# RespirationSchematics.net
KiCad netlist of a schematic drawn in EAGLE
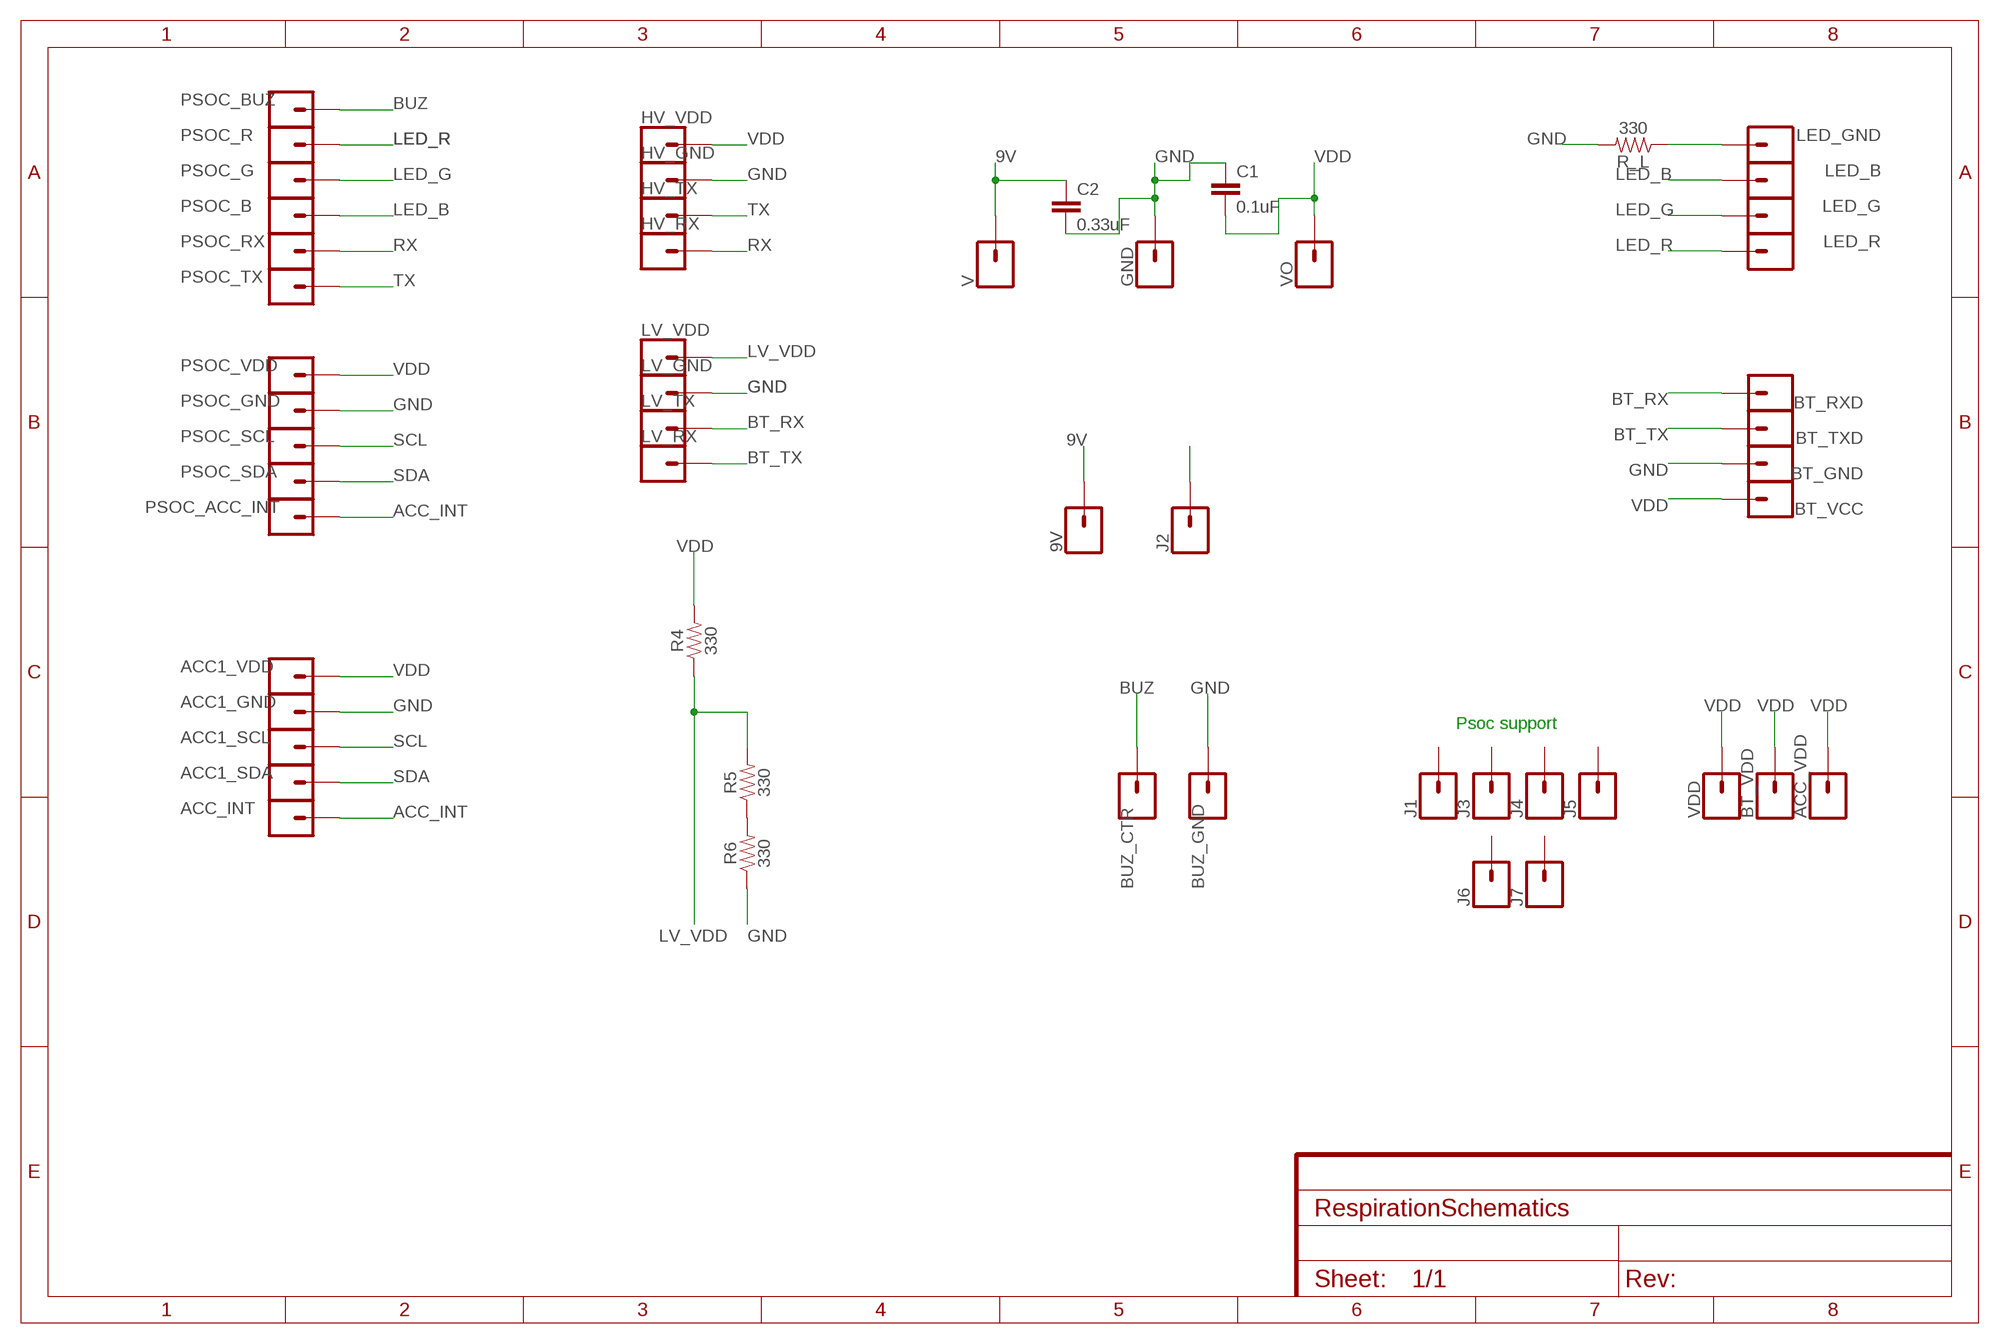
[diagram p0: schematic, sheet 1]

(export (version "E")
  (design (tool "Eeschema 10.0.6"))
  (components
    (comp (ref "9V")
      (value "CONN_01")
      (footprint "eagle-import:1X01")
      (libsource (lib "eagle-import") (part "CONN_01"))
    )
    (comp (ref "ACC1_GND")
      (value "CONN_01")
      (footprint "eagle-import:1X01")
      (libsource (lib "eagle-import") (part "CONN_01"))
    )
    (comp (ref "ACC1_SCL")
      (value "CONN_01")
      (footprint "eagle-import:1X01")
      (libsource (lib "eagle-import") (part "CONN_01"))
    )
    (comp (ref "ACC1_SDA")
      (value "CONN_01")
      (footprint "eagle-import:1X01")
      (libsource (lib "eagle-import") (part "CONN_01"))
    )
    (comp (ref "ACC1_VDD")
      (value "CONN_01")
      (footprint "eagle-import:1X01")
      (libsource (lib "eagle-import") (part "CONN_01"))
    )
    (comp (ref "ACC_INT")
      (value "CONN_01")
      (footprint "eagle-import:1X01")
      (libsource (lib "eagle-import") (part "CONN_01"))
    )
    (comp (ref "ACC_VDD")
      (value "CONN_01")
      (footprint "eagle-import:1X01")
      (libsource (lib "eagle-import") (part "CONN_01"))
    )
    (comp (ref "BT_GND")
      (value "CONN_01")
      (footprint "eagle-import:1X01")
      (libsource (lib "eagle-import") (part "CONN_01"))
    )
    (comp (ref "BT_RXD")
      (value "CONN_01")
      (footprint "eagle-import:1X01")
      (libsource (lib "eagle-import") (part "CONN_01"))
    )
    (comp (ref "BT_TXD")
      (value "CONN_01")
      (footprint "eagle-import:1X01")
      (libsource (lib "eagle-import") (part "CONN_01"))
    )
    (comp (ref "BT_VCC")
      (value "CONN_01")
      (footprint "eagle-import:1X01")
      (libsource (lib "eagle-import") (part "CONN_01"))
    )
    (comp (ref "BT_VDD")
      (value "CONN_01")
      (footprint "eagle-import:1X01")
      (libsource (lib "eagle-import") (part "CONN_01"))
    )
    (comp (ref "BUZ_CTR")
      (value "CONN_01")
      (footprint "eagle-import:1X01")
      (libsource (lib "eagle-import") (part "CONN_01"))
    )
    (comp (ref "BUZ_GND")
      (value "CONN_01")
      (footprint "eagle-import:1X01")
      (libsource (lib "eagle-import") (part "CONN_01"))
    )
    (comp (ref "C1")
      (value "0.1uF")
      (footprint "eagle-import:CAP-PTH-SMALL-KIT")
      (libsource (lib "eagle-import") (part "0.1UF-KIT-EZ-50V-20%"))
    )
    (comp (ref "C2")
      (value "0.33uF")
      (footprint "eagle-import:CAP-PTH-SMALL-KIT")
      (libsource (lib "eagle-import") (part "0.1UF-KIT-EZ-50V-20%"))
    )
    (comp (ref "GND")
      (value "CONN_01")
      (footprint "eagle-import:1X01")
      (libsource (lib "eagle-import") (part "CONN_01"))
    )
    (comp (ref "HV_GND")
      (value "CONN_01")
      (footprint "eagle-import:1X01")
      (libsource (lib "eagle-import") (part "CONN_01"))
    )
    (comp (ref "HV_RX")
      (value "CONN_01")
      (footprint "eagle-import:1X01")
      (libsource (lib "eagle-import") (part "CONN_01"))
    )
    (comp (ref "HV_TX")
      (value "CONN_01")
      (footprint "eagle-import:1X01")
      (libsource (lib "eagle-import") (part "CONN_01"))
    )
    (comp (ref "HV_VDD")
      (value "CONN_01")
      (footprint "eagle-import:1X01")
      (libsource (lib "eagle-import") (part "CONN_01"))
    )
    (comp (ref "J1")
      (value "CONN_01")
      (footprint "eagle-import:1X01")
      (libsource (lib "eagle-import") (part "CONN_01"))
    )
    (comp (ref "J2")
      (value "CONN_01")
      (footprint "eagle-import:1X01")
      (libsource (lib "eagle-import") (part "CONN_01"))
    )
    (comp (ref "J3")
      (value "CONN_01")
      (footprint "eagle-import:1X01")
      (libsource (lib "eagle-import") (part "CONN_01"))
    )
    (comp (ref "J4")
      (value "CONN_01")
      (footprint "eagle-import:1X01")
      (libsource (lib "eagle-import") (part "CONN_01"))
    )
    (comp (ref "J5")
      (value "CONN_01")
      (footprint "eagle-import:1X01")
      (libsource (lib "eagle-import") (part "CONN_01"))
    )
    (comp (ref "J6")
      (value "CONN_01")
      (footprint "eagle-import:1X01")
      (libsource (lib "eagle-import") (part "CONN_01"))
    )
    (comp (ref "J7")
      (value "CONN_01")
      (footprint "eagle-import:1X01")
      (libsource (lib "eagle-import") (part "CONN_01"))
    )
    (comp (ref "LED_B")
      (value "CONN_01")
      (footprint "eagle-import:1X01")
      (libsource (lib "eagle-import") (part "CONN_01"))
    )
    (comp (ref "LED_G")
      (value "CONN_01")
      (footprint "eagle-import:1X01")
      (libsource (lib "eagle-import") (part "CONN_01"))
    )
    (comp (ref "LED_GND")
      (value "CONN_01")
      (footprint "eagle-import:1X01")
      (libsource (lib "eagle-import") (part "CONN_01"))
    )
    (comp (ref "LED_R")
      (value "CONN_01")
      (footprint "eagle-import:1X01")
      (libsource (lib "eagle-import") (part "CONN_01"))
    )
    (comp (ref "LV_GND")
      (value "CONN_01")
      (footprint "eagle-import:1X01")
      (libsource (lib "eagle-import") (part "CONN_01"))
    )
    (comp (ref "LV_RX")
      (value "CONN_01")
      (footprint "eagle-import:1X01")
      (libsource (lib "eagle-import") (part "CONN_01"))
    )
    (comp (ref "LV_TX")
      (value "CONN_01")
      (footprint "eagle-import:1X01")
      (libsource (lib "eagle-import") (part "CONN_01"))
    )
    (comp (ref "LV_VDD")
      (value "CONN_01")
      (footprint "eagle-import:1X01")
      (libsource (lib "eagle-import") (part "CONN_01"))
    )
    (comp (ref "PSOC_ACC_INT")
      (value "CONN_01")
      (footprint "eagle-import:1X01")
      (libsource (lib "eagle-import") (part "CONN_01"))
    )
    (comp (ref "PSOC_B")
      (value "CONN_01")
      (footprint "eagle-import:1X01")
      (libsource (lib "eagle-import") (part "CONN_01"))
    )
    (comp (ref "PSOC_BUZ")
      (value "CONN_01")
      (footprint "eagle-import:1X01")
      (libsource (lib "eagle-import") (part "CONN_01"))
    )
    (comp (ref "PSOC_G")
      (value "CONN_01")
      (footprint "eagle-import:1X01")
      (libsource (lib "eagle-import") (part "CONN_01"))
    )
    (comp (ref "PSOC_GND")
      (value "CONN_01")
      (footprint "eagle-import:1X01")
      (libsource (lib "eagle-import") (part "CONN_01"))
    )
    (comp (ref "PSOC_R")
      (value "CONN_01")
      (footprint "eagle-import:1X01")
      (libsource (lib "eagle-import") (part "CONN_01"))
    )
    (comp (ref "PSOC_RX")
      (value "CONN_01")
      (footprint "eagle-import:1X01")
      (libsource (lib "eagle-import") (part "CONN_01"))
    )
    (comp (ref "PSOC_SCL")
      (value "CONN_01")
      (footprint "eagle-import:1X01")
      (libsource (lib "eagle-import") (part "CONN_01"))
    )
    (comp (ref "PSOC_SDA")
      (value "CONN_01")
      (footprint "eagle-import:1X01")
      (libsource (lib "eagle-import") (part "CONN_01"))
    )
    (comp (ref "PSOC_TX")
      (value "CONN_01")
      (footprint "eagle-import:1X01")
      (libsource (lib "eagle-import") (part "CONN_01"))
    )
    (comp (ref "PSOC_VDD")
      (value "CONN_01")
      (footprint "eagle-import:1X01")
      (libsource (lib "eagle-import") (part "CONN_01"))
    )
    (comp (ref "R4")
      (value "330")
      (footprint "eagle-import:AXIAL-0.3")
      (libsource (lib "eagle-import") (part "330OHM-HORIZ-1/10W-5%"))
    )
    (comp (ref "R5")
      (value "330")
      (footprint "eagle-import:AXIAL-0.3")
      (libsource (lib "eagle-import") (part "330OHM-HORIZ-1/10W-5%"))
    )
    (comp (ref "R6")
      (value "330")
      (footprint "eagle-import:AXIAL-0.3")
      (libsource (lib "eagle-import") (part "330OHM-HORIZ-1/10W-5%"))
    )
    (comp (ref "R_L")
      (value "330")
      (footprint "eagle-import:AXIAL-0.3")
      (libsource (lib "eagle-import") (part "330OHM-HORIZ-1/10W-5%"))
    )
    (comp (ref "V")
      (value "CONN_01")
      (footprint "eagle-import:1X01")
      (libsource (lib "eagle-import") (part "CONN_01"))
    )
    (comp (ref "VDD")
      (value "CONN_01")
      (footprint "eagle-import:1X01")
      (libsource (lib "eagle-import") (part "CONN_01"))
    )
    (comp (ref "VO")
      (value "CONN_01")
      (footprint "eagle-import:1X01")
      (libsource (lib "eagle-import") (part "CONN_01"))
    )
  )
  (nets
    (net (code "1") (name "/9V") (class "Default")
      (node (ref "9V") (pin "1") (pinfunction "1_1") (pintype "passive"))
      (node (ref "C2") (pin "1") (pinfunction "1_1") (pintype "passive"))
      (node (ref "V") (pin "1") (pinfunction "1_1") (pintype "passive"))
    )
    (net (code "2") (name "/ACC_INT") (class "Default")
      (node (ref "ACC_INT") (pin "1") (pinfunction "1_1") (pintype "passive"))
      (node (ref "PSOC_ACC_INT") (pin "1") (pinfunction "1_1") (pintype "passive"))
    )
    (net (code "3") (name "/BT_RX") (class "Default")
      (node (ref "BT_RXD") (pin "1") (pinfunction "1_1") (pintype "passive"))
      (node (ref "LV_TX") (pin "1") (pinfunction "1_1") (pintype "passive"))
    )
    (net (code "4") (name "/BT_TX") (class "Default")
      (node (ref "BT_TXD") (pin "1") (pinfunction "1_1") (pintype "passive"))
      (node (ref "LV_RX") (pin "1") (pinfunction "1_1") (pintype "passive"))
    )
    (net (code "5") (name "/BUZ") (class "Default")
      (node (ref "BUZ_CTR") (pin "1") (pinfunction "1_1") (pintype "passive"))
      (node (ref "PSOC_BUZ") (pin "1") (pinfunction "1_1") (pintype "passive"))
    )
    (net (code "6") (name "/GND") (class "Default")
      (node (ref "ACC1_GND") (pin "1") (pinfunction "1_1") (pintype "passive"))
      (node (ref "BT_GND") (pin "1") (pinfunction "1_1") (pintype "passive"))
      (node (ref "BUZ_GND") (pin "1") (pinfunction "1_1") (pintype "passive"))
      (node (ref "C1") (pin "1") (pinfunction "1_1") (pintype "passive"))
      (node (ref "C2") (pin "2") (pinfunction "2_2") (pintype "passive"))
      (node (ref "GND") (pin "1") (pinfunction "1_1") (pintype "passive"))
      (node (ref "HV_GND") (pin "1") (pinfunction "1_1") (pintype "passive"))
      (node (ref "J2") (pin "1") (pinfunction "1_1") (pintype "passive"))
      (node (ref "LV_GND") (pin "1") (pinfunction "1_1") (pintype "passive"))
      (node (ref "PSOC_GND") (pin "1") (pinfunction "1_1") (pintype "passive"))
      (node (ref "R6") (pin "P$1") (pinfunction "1_P$1") (pintype "passive"))
      (node (ref "R_L") (pin "P$2") (pinfunction "2_P$2") (pintype "passive"))
    )
    (net (code "7") (name "/LED_B") (class "Default")
      (node (ref "LED_B") (pin "1") (pinfunction "1_1") (pintype "passive"))
      (node (ref "PSOC_B") (pin "1") (pinfunction "1_1") (pintype "passive"))
    )
    (net (code "8") (name "/LED_G") (class "Default")
      (node (ref "LED_G") (pin "1") (pinfunction "1_1") (pintype "passive"))
      (node (ref "PSOC_G") (pin "1") (pinfunction "1_1") (pintype "passive"))
    )
    (net (code "9") (name "/LED_R") (class "Default")
      (node (ref "LED_R") (pin "1") (pinfunction "1_1") (pintype "passive"))
      (node (ref "PSOC_R") (pin "1") (pinfunction "1_1") (pintype "passive"))
    )
    (net (code "10") (name "/LV_VDD") (class "Default")
      (node (ref "LV_VDD") (pin "1") (pinfunction "1_1") (pintype "passive"))
      (node (ref "R4") (pin "P$1") (pinfunction "1_P$1") (pintype "passive"))
      (node (ref "R5") (pin "P$2") (pinfunction "2_P$2") (pintype "passive"))
    )
    (net (code "11") (name "/RX") (class "Default")
      (node (ref "HV_RX") (pin "1") (pinfunction "1_1") (pintype "passive"))
      (node (ref "PSOC_RX") (pin "1") (pinfunction "1_1") (pintype "passive"))
    )
    (net (code "12") (name "/SCL") (class "Default")
      (node (ref "ACC1_SCL") (pin "1") (pinfunction "1_1") (pintype "passive"))
      (node (ref "PSOC_SCL") (pin "1") (pinfunction "1_1") (pintype "passive"))
    )
    (net (code "13") (name "/SDA") (class "Default")
      (node (ref "ACC1_SDA") (pin "1") (pinfunction "1_1") (pintype "passive"))
      (node (ref "PSOC_SDA") (pin "1") (pinfunction "1_1") (pintype "passive"))
    )
    (net (code "14") (name "/TX") (class "Default")
      (node (ref "HV_TX") (pin "1") (pinfunction "1_1") (pintype "passive"))
      (node (ref "PSOC_TX") (pin "1") (pinfunction "1_1") (pintype "passive"))
    )
    (net (code "15") (name "/VDD") (class "Default")
      (node (ref "ACC1_VDD") (pin "1") (pinfunction "1_1") (pintype "passive"))
      (node (ref "ACC_VDD") (pin "1") (pinfunction "1_1") (pintype "passive"))
      (node (ref "BT_VCC") (pin "1") (pinfunction "1_1") (pintype "passive"))
      (node (ref "BT_VDD") (pin "1") (pinfunction "1_1") (pintype "passive"))
      (node (ref "C1") (pin "2") (pinfunction "2_2") (pintype "passive"))
      (node (ref "HV_VDD") (pin "1") (pinfunction "1_1") (pintype "passive"))
      (node (ref "PSOC_VDD") (pin "1") (pinfunction "1_1") (pintype "passive"))
      (node (ref "R4") (pin "P$2") (pinfunction "2_P$2") (pintype "passive"))
      (node (ref "VDD") (pin "1") (pinfunction "1_1") (pintype "passive"))
      (node (ref "VO") (pin "1") (pinfunction "1_1") (pintype "passive"))
    )
    (net (code "16") (name "Net-(R5-1)") (class "Default")
      (node (ref "R5") (pin "P$1") (pinfunction "1_P$1") (pintype "passive"))
      (node (ref "R6") (pin "P$2") (pinfunction "2_P$2") (pintype "passive"))
    )
    (net (code "17") (name "Net-(R_L-1)") (class "Default")
      (node (ref "LED_GND") (pin "1") (pinfunction "1_1") (pintype "passive"))
      (node (ref "R_L") (pin "P$1") (pinfunction "1_P$1") (pintype "passive"))
    )
    (net (code "18") (name "unconnected-(J1-Pad1)") (class "Default")
      (node (ref "J1") (pin "1") (pinfunction "1_1") (pintype "passive"))
    )
    (net (code "19") (name "unconnected-(J3-Pad1)") (class "Default")
      (node (ref "J3") (pin "1") (pinfunction "1_1") (pintype "passive"))
    )
    (net (code "20") (name "unconnected-(J4-Pad1)") (class "Default")
      (node (ref "J4") (pin "1") (pinfunction "1_1") (pintype "passive"))
    )
    (net (code "21") (name "unconnected-(J5-Pad1)") (class "Default")
      (node (ref "J5") (pin "1") (pinfunction "1_1") (pintype "passive"))
    )
    (net (code "22") (name "unconnected-(J6-Pad1)") (class "Default")
      (node (ref "J6") (pin "1") (pinfunction "1_1") (pintype "passive"))
    )
    (net (code "23") (name "unconnected-(J7-Pad1)") (class "Default")
      (node (ref "J7") (pin "1") (pinfunction "1_1") (pintype "passive"))
    )
  )
)
